# SectionE_BreakOut.net
KiCad netlist of a schematic drawn in Altium Designer
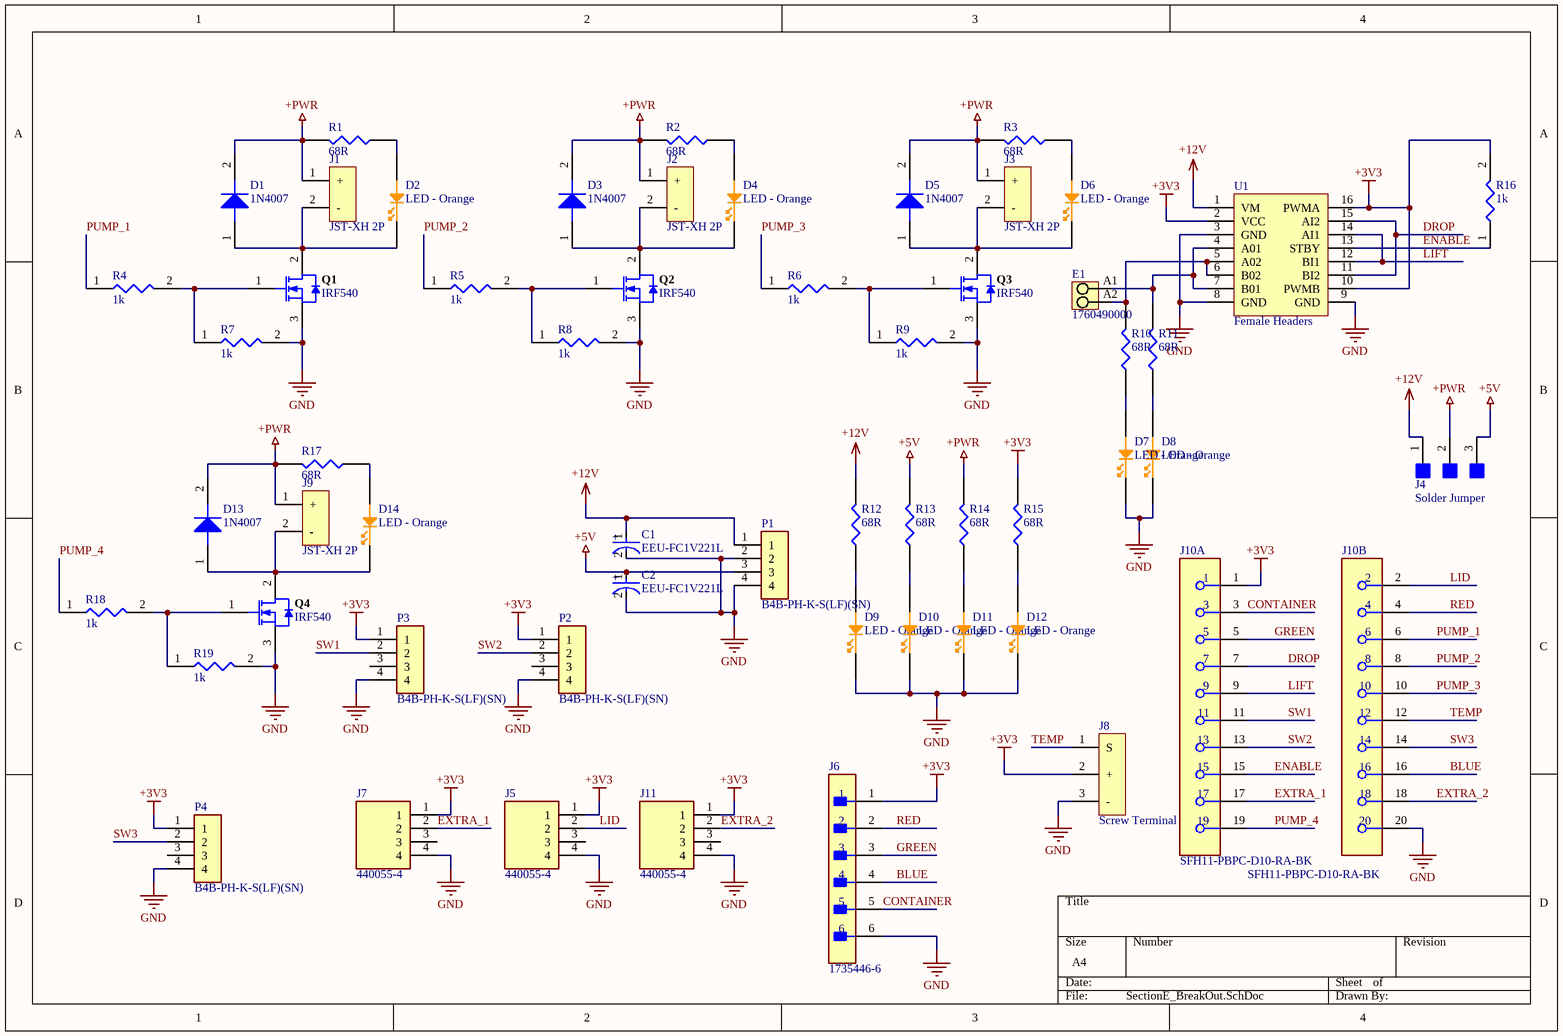
[diagram p0: SectionE_BreakOut.SchDoc]

(export (version "E")
  (design (tool "Eeschema 10.0.6"))
  (components
    (comp (ref "C1")
      (value "EEU-FC1V221L")
      (footprint "FP-EEU-FC1V221L-MFG")
      (description "CAP ALUM 220UF 20% 35V RADIAL")
      (fields
        (field (name "OCTOPART") "https://octopart.com/eeu-fc1v221l-panasonic-39478519")
        (field (name "MANUFACTURER") "Panasonic Electronic Components")
      )
      (libsource (lib "Altium Content Vault") (part "385ce6c70a3ab0aa1e866f00bd8ed49"))
    )
    (comp (ref "C2")
      (value "EEU-FC1V221L")
      (footprint "FP-EEU-FC1V221L-MFG")
      (description "CAP ALUM 220UF 20% 35V RADIAL")
      (fields
        (field (name "OCTOPART") "https://octopart.com/eeu-fc1v221l-panasonic-39478519")
        (field (name "MANUFACTURER") "Panasonic Electronic Components")
      )
      (libsource (lib "Altium Content Vault") (part "385ce6c70a3ab0aa1e866f00bd8ed49"))
    )
    (comp (ref "D1")
      (value "1N4007")
      (footprint "M7 1N4007 SMA")
      (description "1000V 1A Rectifier")
      (fields
        (field (name "MANUFACTURER") "Sangdest Microelectronics")
        (field (name "MANUFACTURER PART NUMBER") "1N4007FLTR")
      )
      (libsource (lib "SectionE_BreakOut") (part "1N4007FLTR"))
    )
    (comp (ref "D2")
      (value "LED - Orange")
      (footprint "LED0603-Orange")
      (description "LED ORANGE CLEAR SMD")
      (fields
        (field (name "MANUFACTURER") "Vishay Lite-On")
        (field (name "MANUFACTURER PART NUMBER") "LTST-C191KFKT")
      )
      (libsource (lib "SectionE_BreakOut") (part "LTST-C191KFKT"))
    )
    (comp (ref "D3")
      (value "1N4007")
      (footprint "M7 1N4007 SMA")
      (description "1000V 1A Rectifier")
      (fields
        (field (name "MANUFACTURER") "Sangdest Microelectronics")
        (field (name "MANUFACTURER PART NUMBER") "1N4007FLTR")
      )
      (libsource (lib "SectionE_BreakOut") (part "1N4007FLTR"))
    )
    (comp (ref "D4")
      (value "LED - Orange")
      (footprint "LED0603-Orange")
      (description "LED ORANGE CLEAR SMD")
      (fields
        (field (name "MANUFACTURER") "Vishay Lite-On")
        (field (name "MANUFACTURER PART NUMBER") "LTST-C191KFKT")
      )
      (libsource (lib "SectionE_BreakOut") (part "LTST-C191KFKT"))
    )
    (comp (ref "D5")
      (value "1N4007")
      (footprint "M7 1N4007 SMA")
      (description "1000V 1A Rectifier")
      (fields
        (field (name "MANUFACTURER") "Sangdest Microelectronics")
        (field (name "MANUFACTURER PART NUMBER") "1N4007FLTR")
      )
      (libsource (lib "SectionE_BreakOut") (part "1N4007FLTR"))
    )
    (comp (ref "D6")
      (value "LED - Orange")
      (footprint "LED0603-Orange")
      (description "LED ORANGE CLEAR SMD")
      (fields
        (field (name "MANUFACTURER") "Vishay Lite-On")
        (field (name "MANUFACTURER PART NUMBER") "LTST-C191KFKT")
      )
      (libsource (lib "SectionE_BreakOut") (part "LTST-C191KFKT"))
    )
    (comp (ref "D7")
      (value "LED - Orange")
      (footprint "LED0603-Orange")
      (description "LED ORANGE CLEAR SMD")
      (fields
        (field (name "MANUFACTURER") "Vishay Lite-On")
        (field (name "MANUFACTURER PART NUMBER") "LTST-C191KFKT")
      )
      (libsource (lib "SectionE_BreakOut") (part "LTST-C191KFKT"))
    )
    (comp (ref "D8")
      (value "LED - Orange")
      (footprint "LED0603-Orange")
      (description "LED ORANGE CLEAR SMD")
      (fields
        (field (name "MANUFACTURER") "Vishay Lite-On")
        (field (name "MANUFACTURER PART NUMBER") "LTST-C191KFKT")
      )
      (libsource (lib "SectionE_BreakOut") (part "LTST-C191KFKT"))
    )
    (comp (ref "D9")
      (value "LED - Orange")
      (footprint "LED0603-Orange")
      (description "LED ORANGE CLEAR SMD")
      (fields
        (field (name "MANUFACTURER") "Vishay Lite-On")
        (field (name "MANUFACTURER PART NUMBER") "LTST-C191KFKT")
      )
      (libsource (lib "SectionE_BreakOut") (part "LTST-C191KFKT"))
    )
    (comp (ref "D10")
      (value "LED - Orange")
      (footprint "LED0603-Orange")
      (description "LED ORANGE CLEAR SMD")
      (fields
        (field (name "MANUFACTURER") "Vishay Lite-On")
        (field (name "MANUFACTURER PART NUMBER") "LTST-C191KFKT")
      )
      (libsource (lib "SectionE_BreakOut") (part "LTST-C191KFKT"))
    )
    (comp (ref "D11")
      (value "LED - Orange")
      (footprint "LED0603-Orange")
      (description "LED ORANGE CLEAR SMD")
      (fields
        (field (name "MANUFACTURER") "Vishay Lite-On")
        (field (name "MANUFACTURER PART NUMBER") "LTST-C191KFKT")
      )
      (libsource (lib "SectionE_BreakOut") (part "LTST-C191KFKT"))
    )
    (comp (ref "D12")
      (value "LED - Orange")
      (footprint "LED0603-Orange")
      (description "LED ORANGE CLEAR SMD")
      (fields
        (field (name "MANUFACTURER") "Vishay Lite-On")
        (field (name "MANUFACTURER PART NUMBER") "LTST-C191KFKT")
      )
      (libsource (lib "SectionE_BreakOut") (part "LTST-C191KFKT"))
    )
    (comp (ref "D13")
      (value "1N4007")
      (footprint "M7 1N4007 SMA")
      (description "1000V 1A Rectifier")
      (fields
        (field (name "MANUFACTURER") "Sangdest Microelectronics")
        (field (name "MANUFACTURER PART NUMBER") "1N4007FLTR")
      )
      (libsource (lib "SectionE_BreakOut") (part "1N4007FLTR"))
    )
    (comp (ref "D14")
      (value "LED - Orange")
      (footprint "LED0603-Orange")
      (description "LED ORANGE CLEAR SMD")
      (fields
        (field (name "MANUFACTURER") "Vishay Lite-On")
        (field (name "MANUFACTURER PART NUMBER") "LTST-C191KFKT")
      )
      (libsource (lib "SectionE_BreakOut") (part "LTST-C191KFKT"))
    )
    (comp (ref "E1")
      (value "1760490000")
      (footprint "PM_5_08_90_02")
      (description "OMNIMATE Signal - series PM")
      (fields (field (name "MANUFACTURER") "Weidmueller"))
      (libsource (lib "Altium Content Vault") (part "Terminal_02_1x02"))
    )
    (comp (ref "J1")
      (value "JST-XH 2P")
      (footprint "JST-XH 2P")
      (description "JST-XH 2 POS 2.5mm Solder ST Thru-Hole Box")
      (fields
        (field (name "MANUFACTURER") "JST")
        (field (name "MANUFACTURER PART NUMBER") "B2B-XH-A(LF)(SN)")
      )
      (libsource (lib "SectionE_BreakOut") (part "B2B-XH-A(LF)(SN)"))
    )
    (comp (ref "J2")
      (value "JST-XH 2P")
      (footprint "JST-XH 2P")
      (description "JST-XH 2 POS 2.5mm Solder ST Thru-Hole Box")
      (fields
        (field (name "MANUFACTURER") "JST")
        (field (name "MANUFACTURER PART NUMBER") "B2B-XH-A(LF)(SN)")
      )
      (libsource (lib "SectionE_BreakOut") (part "B2B-XH-A(LF)(SN)"))
    )
    (comp (ref "J3")
      (value "JST-XH 2P")
      (footprint "JST-XH 2P")
      (description "JST-XH 2 POS 2.5mm Solder ST Thru-Hole Box")
      (fields
        (field (name "MANUFACTURER") "JST")
        (field (name "MANUFACTURER PART NUMBER") "B2B-XH-A(LF)(SN)")
      )
      (libsource (lib "SectionE_BreakOut") (part "B2B-XH-A(LF)(SN)"))
    )
    (comp (ref "J4")
      (value "Solder Jumper")
      (footprint "Solder Jumper")
      (libsource (lib "SectionE_BreakOut") (part "Solder Jumper"))
    )
    (comp (ref "J5")
      (value "440055-4")
      (footprint "TE_440055-4")
      (description "2.0MM,HDR,4POS,R/A")
      (fields (field (name "MF") "TE Connectivity"))
      (libsource (lib "440055-4 (1)") (part "440055-4"))
    )
    (comp (ref "J6")
      (value "1735446-6")
      (footprint "FP-1735446-6-MFG")
      (description "CONN HEADER VERT 6POS 2MM")
      (fields
        (field (name "MANUFACTURER") "TE")
        (field (name "OCTOPART") "https://octopart.com/1735446-6-te+connectivity-42205942")
      )
      (libsource (lib "Altium Content Vault") (part "f2cb566baf1c37ab5a3b8e90bbeafd6"))
    )
    (comp (ref "J7")
      (value "440055-4")
      (footprint "TE_440055-4")
      (description "2.0MM,HDR,4POS,R/A")
      (fields (field (name "MF") "TE Connectivity"))
      (libsource (lib "440055-4 (1)") (part "440055-4"))
    )
    (comp (ref "J8")
      (value "Screw Terminal")
      (footprint "Screw Terminal 3P 5.08MM")
      (description "TERM BLK 3P SIDE ENT 5.08MM PCB")
      (fields
        (field (name "MANUFACTURER") "On-Shore Technology")
        (field (name "MANUFACTURER PART NUMBER") "OSTTC032162")
      )
      (libsource (lib "SectionE_BreakOut") (part "OSTTC032162"))
    )
    (comp (ref "J9")
      (value "JST-XH 2P")
      (footprint "JST-XH 2P")
      (description "JST-XH 2 POS 2.5mm Solder ST Thru-Hole Box")
      (fields
        (field (name "MANUFACTURER") "JST")
        (field (name "MANUFACTURER PART NUMBER") "B2B-XH-A(LF)(SN)")
      )
      (libsource (lib "SectionE_BreakOut") (part "B2B-XH-A(LF)(SN)"))
    )
    (comp (ref "J10")
      (value "SFH11-PBPC-D10-RA-BK")
      (footprint "FP-SFH11-PBPC-D10-RA-BK-MFG")
      (description "CONN HDR 20POS 0.1 GOLD PCB R/A")
      (fields
        (field (name "OCTOPART") "https://octopart.com/sfh11-pbpc-d10-ra-bk-sullins-12270496")
        (field (name "MANUFACTURER") "Sullins")
      )
      (libsource (lib "Altium Content Vault") (part "86e307fb827e6da12e54f1dde2f44ab"))
    )
    (comp (ref "J11")
      (value "440055-4")
      (footprint "TE_440055-4")
      (description "2.0MM,HDR,4POS,R/A")
      (fields (field (name "MF") "TE Connectivity"))
      (libsource (lib "440055-4 (1)") (part "440055-4"))
    )
    (comp (ref "P1")
      (value "B4B-PH-K-S(LF)(SN)")
      (footprint "JST_B4B-PH-K-S(LF)(SN)")
      (description "Connector Header Through Hole 4 position 0.079 _2.00mm_")
      (fields (field (name "MP") "B4B-PH-K-S_LF__SN_") (field (name "DIGI-KEY_PART_NUMBER") "455-1706-ND"))
      (libsource (lib "SnapEDAsch") (part "B4B-PH-K-S(LF)(SN)"))
    )
    (comp (ref "P2")
      (value "B4B-PH-K-S(LF)(SN)")
      (footprint "JST_B4B-PH-K-S(LF)(SN)")
      (description "Connector Header Through Hole 4 position 0.079 _2.00mm_")
      (fields (field (name "MP") "B4B-PH-K-S_LF__SN_") (field (name "DIGI-KEY_PART_NUMBER") "455-1706-ND"))
      (libsource (lib "SnapEDAsch") (part "B4B-PH-K-S(LF)(SN)"))
    )
    (comp (ref "P3")
      (value "B4B-PH-K-S(LF)(SN)")
      (footprint "JST_B4B-PH-K-S(LF)(SN)")
      (description "Connector Header Through Hole 4 position 0.079 _2.00mm_")
      (fields (field (name "MP") "B4B-PH-K-S_LF__SN_") (field (name "DIGI-KEY_PART_NUMBER") "455-1706-ND"))
      (libsource (lib "SnapEDAsch") (part "B4B-PH-K-S(LF)(SN)"))
    )
    (comp (ref "P4")
      (value "B4B-PH-K-S(LF)(SN)")
      (footprint "JST_B4B-PH-K-S(LF)(SN)")
      (description "Connector Header Through Hole 4 position 0.079 _2.00mm_")
      (fields (field (name "MP") "B4B-PH-K-S_LF__SN_") (field (name "DIGI-KEY_PART_NUMBER") "455-1706-ND"))
      (libsource (lib "SnapEDAsch") (part "B4B-PH-K-S(LF)(SN)"))
    )
    (comp (ref "Q1")
      (value "IRF540")
      (footprint "VISH-TO-220AB-3_A")
      (description "Power MOSFET, 100 VDS, -55 to 175 degC, 3-Pin TO-220AB, RoHS, Tube")
      (fields (field (name "MANUFACTURER") "Vishay"))
      (libsource (lib "Altium Content Vault") (part "NEMOS-GDS-3"))
    )
    (comp (ref "Q2")
      (value "IRF540")
      (footprint "VISH-TO-220AB-3_A")
      (description "Power MOSFET, 100 VDS, -55 to 175 degC, 3-Pin TO-220AB, RoHS, Tube")
      (fields (field (name "MANUFACTURER") "Vishay"))
      (libsource (lib "Altium Content Vault") (part "NEMOS-GDS-3"))
    )
    (comp (ref "Q3")
      (value "IRF540")
      (footprint "VISH-TO-220AB-3_A")
      (description "Power MOSFET, 100 VDS, -55 to 175 degC, 3-Pin TO-220AB, RoHS, Tube")
      (fields (field (name "MANUFACTURER") "Vishay"))
      (libsource (lib "Altium Content Vault") (part "NEMOS-GDS-3"))
    )
    (comp (ref "Q4")
      (value "IRF540")
      (footprint "VISH-TO-220AB-3_A")
      (description "Power MOSFET, 100 VDS, -55 to 175 degC, 3-Pin TO-220AB, RoHS, Tube")
      (fields (field (name "MANUFACTURER") "Vishay"))
      (libsource (lib "Altium Content Vault") (part "NEMOS-GDS-3"))
    )
    (comp (ref "R1")
      (value "68R")
      (footprint "68R 0603")
      (description "CRGP 0603 68R 1%")
      (fields
        (field (name "MANUFACTURER") "TE Connectivity")
        (field (name "MANUFACTURER PART NUMBER") "CRGP0603F68R")
      )
      (libsource (lib "SectionE_BreakOut") (part "CRGP0603F68R"))
    )
    (comp (ref "R2")
      (value "68R")
      (footprint "68R 0603")
      (description "CRGP 0603 68R 1%")
      (fields
        (field (name "MANUFACTURER") "TE Connectivity")
        (field (name "MANUFACTURER PART NUMBER") "CRGP0603F68R")
      )
      (libsource (lib "SectionE_BreakOut") (part "CRGP0603F68R"))
    )
    (comp (ref "R3")
      (value "68R")
      (footprint "68R 0603")
      (description "CRGP 0603 68R 1%")
      (fields
        (field (name "MANUFACTURER") "TE Connectivity")
        (field (name "MANUFACTURER PART NUMBER") "CRGP0603F68R")
      )
      (libsource (lib "SectionE_BreakOut") (part "CRGP0603F68R"))
    )
    (comp (ref "R4")
      (value "1k")
      (footprint "R0603 1k")
      (description "0603 1k Ohm 1% 1/10W")
      (fields
        (field (name "MANUFACTURER") "TE Connectivity")
        (field (name "MANUFACTURER PART NUMBER") "CRGCQ0603F1K0")
      )
      (libsource (lib "SectionE_BreakOut") (part "CRGCQ0603F1K0"))
    )
    (comp (ref "R5")
      (value "1k")
      (footprint "R0603 1k")
      (description "0603 1k Ohm 1% 1/10W")
      (fields
        (field (name "MANUFACTURER") "TE Connectivity")
        (field (name "MANUFACTURER PART NUMBER") "CRGCQ0603F1K0")
      )
      (libsource (lib "SectionE_BreakOut") (part "CRGCQ0603F1K0"))
    )
    (comp (ref "R6")
      (value "1k")
      (footprint "R0603 1k")
      (description "0603 1k Ohm 1% 1/10W")
      (fields
        (field (name "MANUFACTURER") "TE Connectivity")
        (field (name "MANUFACTURER PART NUMBER") "CRGCQ0603F1K0")
      )
      (libsource (lib "SectionE_BreakOut") (part "CRGCQ0603F1K0"))
    )
    (comp (ref "R7")
      (value "1k")
      (footprint "R0603 1k")
      (description "0603 1k Ohm 1% 1/10W")
      (fields
        (field (name "MANUFACTURER") "TE Connectivity")
        (field (name "MANUFACTURER PART NUMBER") "CRGCQ0603F1K0")
      )
      (libsource (lib "SectionE_BreakOut") (part "CRGCQ0603F1K0"))
    )
    (comp (ref "R8")
      (value "1k")
      (footprint "R0603 1k")
      (description "0603 1k Ohm 1% 1/10W")
      (fields
        (field (name "MANUFACTURER") "TE Connectivity")
        (field (name "MANUFACTURER PART NUMBER") "CRGCQ0603F1K0")
      )
      (libsource (lib "SectionE_BreakOut") (part "CRGCQ0603F1K0"))
    )
    (comp (ref "R9")
      (value "1k")
      (footprint "R0603 1k")
      (description "0603 1k Ohm 1% 1/10W")
      (fields
        (field (name "MANUFACTURER") "TE Connectivity")
        (field (name "MANUFACTURER PART NUMBER") "CRGCQ0603F1K0")
      )
      (libsource (lib "SectionE_BreakOut") (part "CRGCQ0603F1K0"))
    )
    (comp (ref "R10")
      (value "68R")
      (footprint "68R 0603")
      (description "CRGP 0603 68R 1%")
      (fields
        (field (name "MANUFACTURER") "TE Connectivity")
        (field (name "MANUFACTURER PART NUMBER") "CRGP0603F68R")
      )
      (libsource (lib "SectionE_BreakOut") (part "CRGP0603F68R"))
    )
    (comp (ref "R11")
      (value "68R")
      (footprint "68R 0603")
      (description "CRGP 0603 68R 1%")
      (fields
        (field (name "MANUFACTURER") "TE Connectivity")
        (field (name "MANUFACTURER PART NUMBER") "CRGP0603F68R")
      )
      (libsource (lib "SectionE_BreakOut") (part "CRGP0603F68R"))
    )
    (comp (ref "R12")
      (value "68R")
      (footprint "68R 0603")
      (description "CRGP 0603 68R 1%")
      (fields
        (field (name "MANUFACTURER") "TE Connectivity")
        (field (name "MANUFACTURER PART NUMBER") "CRGP0603F68R")
      )
      (libsource (lib "SectionE_BreakOut") (part "CRGP0603F68R"))
    )
    (comp (ref "R13")
      (value "68R")
      (footprint "68R 0603")
      (description "CRGP 0603 68R 1%")
      (fields
        (field (name "MANUFACTURER") "TE Connectivity")
        (field (name "MANUFACTURER PART NUMBER") "CRGP0603F68R")
      )
      (libsource (lib "SectionE_BreakOut") (part "CRGP0603F68R"))
    )
    (comp (ref "R14")
      (value "68R")
      (footprint "68R 0603")
      (description "CRGP 0603 68R 1%")
      (fields
        (field (name "MANUFACTURER") "TE Connectivity")
        (field (name "MANUFACTURER PART NUMBER") "CRGP0603F68R")
      )
      (libsource (lib "SectionE_BreakOut") (part "CRGP0603F68R"))
    )
    (comp (ref "R15")
      (value "68R")
      (footprint "68R 0603")
      (description "CRGP 0603 68R 1%")
      (fields
        (field (name "MANUFACTURER") "TE Connectivity")
        (field (name "MANUFACTURER PART NUMBER") "CRGP0603F68R")
      )
      (libsource (lib "SectionE_BreakOut") (part "CRGP0603F68R"))
    )
    (comp (ref "R16")
      (value "1k")
      (footprint "R0603 1k")
      (description "0603 1k Ohm 1% 1/10W")
      (fields
        (field (name "MANUFACTURER") "TE Connectivity")
        (field (name "MANUFACTURER PART NUMBER") "CRGCQ0603F1K0")
      )
      (libsource (lib "SectionE_BreakOut") (part "CRGCQ0603F1K0"))
    )
    (comp (ref "R17")
      (value "68R")
      (footprint "68R 0603")
      (description "CRGP 0603 68R 1%")
      (fields
        (field (name "MANUFACTURER") "TE Connectivity")
        (field (name "MANUFACTURER PART NUMBER") "CRGP0603F68R")
      )
      (libsource (lib "SectionE_BreakOut") (part "CRGP0603F68R"))
    )
    (comp (ref "R18")
      (value "1k")
      (footprint "R0603 1k")
      (description "0603 1k Ohm 1% 1/10W")
      (fields
        (field (name "MANUFACTURER") "TE Connectivity")
        (field (name "MANUFACTURER PART NUMBER") "CRGCQ0603F1K0")
      )
      (libsource (lib "SectionE_BreakOut") (part "CRGCQ0603F1K0"))
    )
    (comp (ref "R19")
      (value "1k")
      (footprint "R0603 1k")
      (description "0603 1k Ohm 1% 1/10W")
      (fields
        (field (name "MANUFACTURER") "TE Connectivity")
        (field (name "MANUFACTURER PART NUMBER") "CRGCQ0603F1K0")
      )
      (libsource (lib "SectionE_BreakOut") (part "CRGCQ0603F1K0"))
    )
    (comp (ref "U1")
      (value "Female Headers")
      (footprint "TB6612FNG")
      (description "Motor Driver")
      (libsource (lib "SectionE_BreakOut") (part "TB6612FNG Female"))
    )
  )
  (nets
    (net (code "1") (name "+3V3") (class "Default")
      (node (ref "J10") (pin "1") (pinfunction "1_1") (pintype "passive"))
      (node (ref "J11") (pin "1") (pinfunction "1_1") (pintype "passive"))
      (node (ref "J5") (pin "1") (pinfunction "1_1") (pintype "passive"))
      (node (ref "J6") (pin "1") (pinfunction "1_1") (pintype "passive"))
      (node (ref "J7") (pin "1") (pinfunction "1_1") (pintype "passive"))
      (node (ref "J8") (pin "2") (pinfunction "+_2") (pintype "passive"))
      (node (ref "P2") (pin "1") (pinfunction "1_1") (pintype "passive"))
      (node (ref "P3") (pin "1") (pinfunction "1_1") (pintype "passive"))
      (node (ref "P4") (pin "1") (pinfunction "1_1") (pintype "passive"))
      (node (ref "R15") (pin "2") (pinfunction "2_2") (pintype "passive"))
      (node (ref "R16") (pin "2") (pinfunction "2_2") (pintype "passive"))
      (node (ref "U1") (pin "10") (pinfunction "PWMB_10") (pintype "passive"))
      (node (ref "U1") (pin "16") (pinfunction "PWMA_16") (pintype "passive"))
      (node (ref "U1") (pin "2") (pinfunction "VCC_2") (pintype "passive"))
    )
    (net (code "2") (name "+5V") (class "Default")
      (node (ref "C2") (pin "1") (pinfunction "C_1") (pintype "passive"))
      (node (ref "J4") (pin "3") (pinfunction "3_3") (pintype "passive"))
      (node (ref "P1") (pin "3") (pinfunction "3_3") (pintype "passive"))
      (node (ref "R13") (pin "2") (pinfunction "2_2") (pintype "passive"))
    )
    (net (code "3") (name "+12V") (class "Default")
      (node (ref "C1") (pin "1") (pinfunction "C_1") (pintype "passive"))
      (node (ref "J4") (pin "1") (pinfunction "1_1") (pintype "passive"))
      (node (ref "P1") (pin "1") (pinfunction "1_1") (pintype "passive"))
      (node (ref "R12") (pin "2") (pinfunction "2_2") (pintype "passive"))
      (node (ref "U1") (pin "1") (pinfunction "VM_1") (pintype "passive"))
    )
    (net (code "4") (name "+PWR") (class "Default")
      (node (ref "D1") (pin "2") (pinfunction "Cathode_2") (pintype "passive"))
      (node (ref "D13") (pin "2") (pinfunction "Cathode_2") (pintype "passive"))
      (node (ref "D3") (pin "2") (pinfunction "Cathode_2") (pintype "passive"))
      (node (ref "D5") (pin "2") (pinfunction "Cathode_2") (pintype "passive"))
      (node (ref "J1") (pin "1") (pinfunction "+_1") (pintype "passive"))
      (node (ref "J2") (pin "1") (pinfunction "+_1") (pintype "passive"))
      (node (ref "J3") (pin "1") (pinfunction "+_1") (pintype "passive"))
      (node (ref "J4") (pin "2") (pinfunction "2_2") (pintype "passive"))
      (node (ref "J9") (pin "1") (pinfunction "+_1") (pintype "passive"))
      (node (ref "R1") (pin "2") (pinfunction "2_2") (pintype "passive"))
      (node (ref "R14") (pin "2") (pinfunction "2_2") (pintype "passive"))
      (node (ref "R17") (pin "2") (pinfunction "2_2") (pintype "passive"))
      (node (ref "R2") (pin "2") (pinfunction "2_2") (pintype "passive"))
      (node (ref "R3") (pin "2") (pinfunction "2_2") (pintype "passive"))
    )
    (net (code "5") (name "/BLUE") (class "Default")
      (node (ref "J10") (pin "16") (pinfunction "16_16") (pintype "passive"))
      (node (ref "J6") (pin "4") (pinfunction "4_4") (pintype "passive"))
    )
    (net (code "6") (name "/CONTAINER") (class "Default")
      (node (ref "J10") (pin "3") (pinfunction "3_3") (pintype "passive"))
      (node (ref "J6") (pin "5") (pinfunction "5_5") (pintype "passive"))
    )
    (net (code "7") (name "/DROP") (class "Default")
      (node (ref "J10") (pin "7") (pinfunction "7_7") (pintype "passive"))
      (node (ref "U1") (pin "11") (pinfunction "BI2_11") (pintype "passive"))
      (node (ref "U1") (pin "15") (pinfunction "AI2_15") (pintype "passive"))
    )
    (net (code "8") (name "/ENABLE") (class "Default")
      (node (ref "J10") (pin "15") (pinfunction "15_15") (pintype "passive"))
      (node (ref "R16") (pin "1") (pinfunction "1_1") (pintype "passive"))
      (node (ref "U1") (pin "13") (pinfunction "STBY_13") (pintype "passive"))
    )
    (net (code "9") (name "/EXTRA_1") (class "Default")
      (node (ref "J10") (pin "17") (pinfunction "17_17") (pintype "passive"))
      (node (ref "J7") (pin "2") (pinfunction "2_2") (pintype "passive"))
    )
    (net (code "10") (name "/EXTRA_2") (class "Default")
      (node (ref "J10") (pin "18") (pinfunction "18_18") (pintype "passive"))
      (node (ref "J11") (pin "2") (pinfunction "2_2") (pintype "passive"))
    )
    (net (code "11") (name "/GREEN") (class "Default")
      (node (ref "J10") (pin "5") (pinfunction "5_5") (pintype "passive"))
      (node (ref "J6") (pin "3") (pinfunction "3_3") (pintype "passive"))
    )
    (net (code "12") (name "/LID") (class "Default")
      (node (ref "J10") (pin "2") (pinfunction "2_2") (pintype "passive"))
      (node (ref "J5") (pin "2") (pinfunction "2_2") (pintype "passive"))
    )
    (net (code "13") (name "/LIFT") (class "Default")
      (node (ref "J10") (pin "9") (pinfunction "9_9") (pintype "passive"))
      (node (ref "U1") (pin "12") (pinfunction "BI1_12") (pintype "passive"))
      (node (ref "U1") (pin "14") (pinfunction "AI1_14") (pintype "passive"))
    )
    (net (code "14") (name "/PUMP_1") (class "Default")
      (node (ref "J10") (pin "6") (pinfunction "6_6") (pintype "passive"))
      (node (ref "R4") (pin "1") (pinfunction "1_1") (pintype "passive"))
    )
    (net (code "15") (name "/PUMP_2") (class "Default")
      (node (ref "J10") (pin "8") (pinfunction "8_8") (pintype "passive"))
      (node (ref "R5") (pin "1") (pinfunction "1_1") (pintype "passive"))
    )
    (net (code "16") (name "/PUMP_3") (class "Default")
      (node (ref "J10") (pin "10") (pinfunction "10_10") (pintype "passive"))
      (node (ref "R6") (pin "1") (pinfunction "1_1") (pintype "passive"))
    )
    (net (code "17") (name "/PUMP_4") (class "Default")
      (node (ref "J10") (pin "19") (pinfunction "19_19") (pintype "passive"))
      (node (ref "R18") (pin "1") (pinfunction "1_1") (pintype "passive"))
    )
    (net (code "18") (name "/RED") (class "Default")
      (node (ref "J10") (pin "4") (pinfunction "4_4") (pintype "passive"))
      (node (ref "J6") (pin "2") (pinfunction "2_2") (pintype "passive"))
    )
    (net (code "19") (name "/SW1") (class "Default")
      (node (ref "J10") (pin "11") (pinfunction "11_11") (pintype "passive"))
      (node (ref "P3") (pin "2") (pinfunction "2_2") (pintype "passive"))
    )
    (net (code "20") (name "/SW2") (class "Default")
      (node (ref "J10") (pin "13") (pinfunction "13_13") (pintype "passive"))
      (node (ref "P2") (pin "2") (pinfunction "2_2") (pintype "passive"))
    )
    (net (code "21") (name "/SW3") (class "Default")
      (node (ref "J10") (pin "14") (pinfunction "14_14") (pintype "passive"))
      (node (ref "P4") (pin "2") (pinfunction "2_2") (pintype "passive"))
    )
    (net (code "22") (name "/TEMP") (class "Default")
      (node (ref "J10") (pin "12") (pinfunction "12_12") (pintype "passive"))
      (node (ref "J8") (pin "1") (pinfunction "S_1") (pintype "passive"))
    )
    (net (code "23") (name "GND") (class "Default")
      (node (ref "C1") (pin "2") (pinfunction "A_2") (pintype "passive"))
      (node (ref "C2") (pin "2") (pinfunction "A_2") (pintype "passive"))
      (node (ref "D10") (pin "1") (pinfunction "Cathode_1") (pintype "passive"))
      (node (ref "D11") (pin "1") (pinfunction "Cathode_1") (pintype "passive"))
      (node (ref "D12") (pin "1") (pinfunction "Cathode_1") (pintype "passive"))
      (node (ref "D7") (pin "1") (pinfunction "Cathode_1") (pintype "passive"))
      (node (ref "D8") (pin "1") (pinfunction "Cathode_1") (pintype "passive"))
      (node (ref "D9") (pin "1") (pinfunction "Cathode_1") (pintype "passive"))
      (node (ref "J10") (pin "20") (pinfunction "20_20") (pintype "passive"))
      (node (ref "J11") (pin "4") (pinfunction "4_4") (pintype "passive"))
      (node (ref "J5") (pin "4") (pinfunction "4_4") (pintype "passive"))
      (node (ref "J6") (pin "6") (pinfunction "6_6") (pintype "passive"))
      (node (ref "J7") (pin "4") (pinfunction "4_4") (pintype "passive"))
      (node (ref "J8") (pin "3") (pinfunction "-_3") (pintype "passive"))
      (node (ref "P1") (pin "2") (pinfunction "2_2") (pintype "passive"))
      (node (ref "P1") (pin "4") (pinfunction "4_4") (pintype "passive"))
      (node (ref "P2") (pin "4") (pinfunction "4_4") (pintype "passive"))
      (node (ref "P3") (pin "4") (pinfunction "4_4") (pintype "passive"))
      (node (ref "P4") (pin "4") (pinfunction "4_4") (pintype "passive"))
      (node (ref "Q1") (pin "3") (pinfunction "S_3") (pintype "passive"))
      (node (ref "Q2") (pin "3") (pinfunction "S_3") (pintype "passive"))
      (node (ref "Q3") (pin "3") (pinfunction "S_3") (pintype "passive"))
      (node (ref "Q4") (pin "3") (pinfunction "S_3") (pintype "passive"))
      (node (ref "R19") (pin "2") (pinfunction "2_2") (pintype "passive"))
      (node (ref "R7") (pin "2") (pinfunction "2_2") (pintype "passive"))
      (node (ref "R8") (pin "2") (pinfunction "2_2") (pintype "passive"))
      (node (ref "R9") (pin "2") (pinfunction "2_2") (pintype "passive"))
      (node (ref "U1") (pin "3") (pinfunction "GND_3") (pintype "passive"))
      (node (ref "U1") (pin "8") (pinfunction "GND_8") (pintype "passive"))
      (node (ref "U1") (pin "9") (pinfunction "GND_9") (pintype "passive"))
    )
    (net (code "24") (name "Net-(D1-Anode)") (class "Default")
      (node (ref "D1") (pin "1") (pinfunction "Anode_1") (pintype "passive"))
      (node (ref "D2") (pin "1") (pinfunction "Cathode_1") (pintype "passive"))
      (node (ref "J1") (pin "2") (pinfunction "-_2") (pintype "passive"))
      (node (ref "Q1") (pin "2") (pinfunction "D_2") (pintype "passive"))
    )
    (net (code "25") (name "Net-(D2-Anode)") (class "Default")
      (node (ref "D2") (pin "2") (pinfunction "Anode_2") (pintype "passive"))
      (node (ref "R1") (pin "1") (pinfunction "1_1") (pintype "passive"))
    )
    (net (code "26") (name "Net-(D3-Anode)") (class "Default")
      (node (ref "D3") (pin "1") (pinfunction "Anode_1") (pintype "passive"))
      (node (ref "D4") (pin "1") (pinfunction "Cathode_1") (pintype "passive"))
      (node (ref "J2") (pin "2") (pinfunction "-_2") (pintype "passive"))
      (node (ref "Q2") (pin "2") (pinfunction "D_2") (pintype "passive"))
    )
    (net (code "27") (name "Net-(D4-Anode)") (class "Default")
      (node (ref "D4") (pin "2") (pinfunction "Anode_2") (pintype "passive"))
      (node (ref "R2") (pin "1") (pinfunction "1_1") (pintype "passive"))
    )
    (net (code "28") (name "Net-(D5-Anode)") (class "Default")
      (node (ref "D5") (pin "1") (pinfunction "Anode_1") (pintype "passive"))
      (node (ref "D6") (pin "1") (pinfunction "Cathode_1") (pintype "passive"))
      (node (ref "J3") (pin "2") (pinfunction "-_2") (pintype "passive"))
      (node (ref "Q3") (pin "2") (pinfunction "D_2") (pintype "passive"))
    )
    (net (code "29") (name "Net-(D6-Anode)") (class "Default")
      (node (ref "D6") (pin "2") (pinfunction "Anode_2") (pintype "passive"))
      (node (ref "R3") (pin "1") (pinfunction "1_1") (pintype "passive"))
    )
    (net (code "30") (name "Net-(D7-Anode)") (class "Default")
      (node (ref "D7") (pin "2") (pinfunction "Anode_2") (pintype "passive"))
      (node (ref "R10") (pin "1") (pinfunction "1_1") (pintype "passive"))
    )
    (net (code "31") (name "Net-(D8-Anode)") (class "Default")
      (node (ref "D8") (pin "2") (pinfunction "Anode_2") (pintype "passive"))
      (node (ref "R11") (pin "1") (pinfunction "1_1") (pintype "passive"))
    )
    (net (code "32") (name "Net-(D9-Anode)") (class "Default")
      (node (ref "D9") (pin "2") (pinfunction "Anode_2") (pintype "passive"))
      (node (ref "R12") (pin "1") (pinfunction "1_1") (pintype "passive"))
    )
    (net (code "33") (name "Net-(D10-Anode)") (class "Default")
      (node (ref "D10") (pin "2") (pinfunction "Anode_2") (pintype "passive"))
      (node (ref "R13") (pin "1") (pinfunction "1_1") (pintype "passive"))
    )
    (net (code "34") (name "Net-(D11-Anode)") (class "Default")
      (node (ref "D11") (pin "2") (pinfunction "Anode_2") (pintype "passive"))
      (node (ref "R14") (pin "1") (pinfunction "1_1") (pintype "passive"))
    )
    (net (code "35") (name "Net-(D12-Anode)") (class "Default")
      (node (ref "D12") (pin "2") (pinfunction "Anode_2") (pintype "passive"))
      (node (ref "R15") (pin "1") (pinfunction "1_1") (pintype "passive"))
    )
    (net (code "36") (name "Net-(D13-Anode)") (class "Default")
      (node (ref "D13") (pin "1") (pinfunction "Anode_1") (pintype "passive"))
      (node (ref "D14") (pin "1") (pinfunction "Cathode_1") (pintype "passive"))
      (node (ref "J9") (pin "2") (pinfunction "-_2") (pintype "passive"))
      (node (ref "Q4") (pin "2") (pinfunction "D_2") (pintype "passive"))
    )
    (net (code "37") (name "Net-(D14-Anode)") (class "Default")
      (node (ref "D14") (pin "2") (pinfunction "Anode_2") (pintype "passive"))
      (node (ref "R17") (pin "1") (pinfunction "1_1") (pintype "passive"))
    )
    (net (code "38") (name "Net-(Q1-G)") (class "Default")
      (node (ref "Q1") (pin "1") (pinfunction "G_1") (pintype "passive"))
      (node (ref "R4") (pin "2") (pinfunction "2_2") (pintype "passive"))
      (node (ref "R7") (pin "1") (pinfunction "1_1") (pintype "passive"))
    )
    (net (code "39") (name "Net-(Q2-G)") (class "Default")
      (node (ref "Q2") (pin "1") (pinfunction "G_1") (pintype "passive"))
      (node (ref "R5") (pin "2") (pinfunction "2_2") (pintype "passive"))
      (node (ref "R8") (pin "1") (pinfunction "1_1") (pintype "passive"))
    )
    (net (code "40") (name "Net-(Q3-G)") (class "Default")
      (node (ref "Q3") (pin "1") (pinfunction "G_1") (pintype "passive"))
      (node (ref "R6") (pin "2") (pinfunction "2_2") (pintype "passive"))
      (node (ref "R9") (pin "1") (pinfunction "1_1") (pintype "passive"))
    )
    (net (code "41") (name "Net-(Q4-G)") (class "Default")
      (node (ref "Q4") (pin "1") (pinfunction "G_1") (pintype "passive"))
      (node (ref "R18") (pin "2") (pinfunction "2_2") (pintype "passive"))
      (node (ref "R19") (pin "1") (pinfunction "1_1") (pintype "passive"))
    )
    (net (code "42") (name "Net-(U1-A01)") (class "Default")
      (node (ref "E1") (pin "A1") (pinfunction "A1_A1") (pintype "passive"))
      (node (ref "R11") (pin "2") (pinfunction "2_2") (pintype "passive"))
      (node (ref "U1") (pin "4") (pinfunction "A01_4") (pintype "passive"))
      (node (ref "U1") (pin "7") (pinfunction "B01_7") (pintype "passive"))
    )
    (net (code "43") (name "Net-(U1-A02)") (class "Default")
      (node (ref "E1") (pin "A2") (pinfunction "A2_A2") (pintype "passive"))
      (node (ref "R10") (pin "2") (pinfunction "2_2") (pintype "passive"))
      (node (ref "U1") (pin "5") (pinfunction "A02_5") (pintype "passive"))
      (node (ref "U1") (pin "6") (pinfunction "B02_6") (pintype "passive"))
    )
    (net (code "44") (name "unconnected-(J5-Pad3)") (class "Default")
      (node (ref "J5") (pin "3") (pinfunction "3_3") (pintype "passive"))
    )
    (net (code "45") (name "unconnected-(J7-Pad3)") (class "Default")
      (node (ref "J7") (pin "3") (pinfunction "3_3") (pintype "passive"))
    )
    (net (code "46") (name "unconnected-(J11-Pad3)") (class "Default")
      (node (ref "J11") (pin "3") (pinfunction "3_3") (pintype "passive"))
    )
    (net (code "47") (name "unconnected-(P2-Pad3)") (class "Default")
      (node (ref "P2") (pin "3") (pinfunction "3_3") (pintype "passive"))
    )
    (net (code "48") (name "unconnected-(P3-Pad3)") (class "Default")
      (node (ref "P3") (pin "3") (pinfunction "3_3") (pintype "passive"))
    )
    (net (code "49") (name "unconnected-(P4-Pad3)") (class "Default")
      (node (ref "P4") (pin "3") (pinfunction "3_3") (pintype "passive"))
    )
  )
)
